# SCH_10_1HD_2021-11-26.net
KiCad netlist of a schematic drawn in EasyEDA
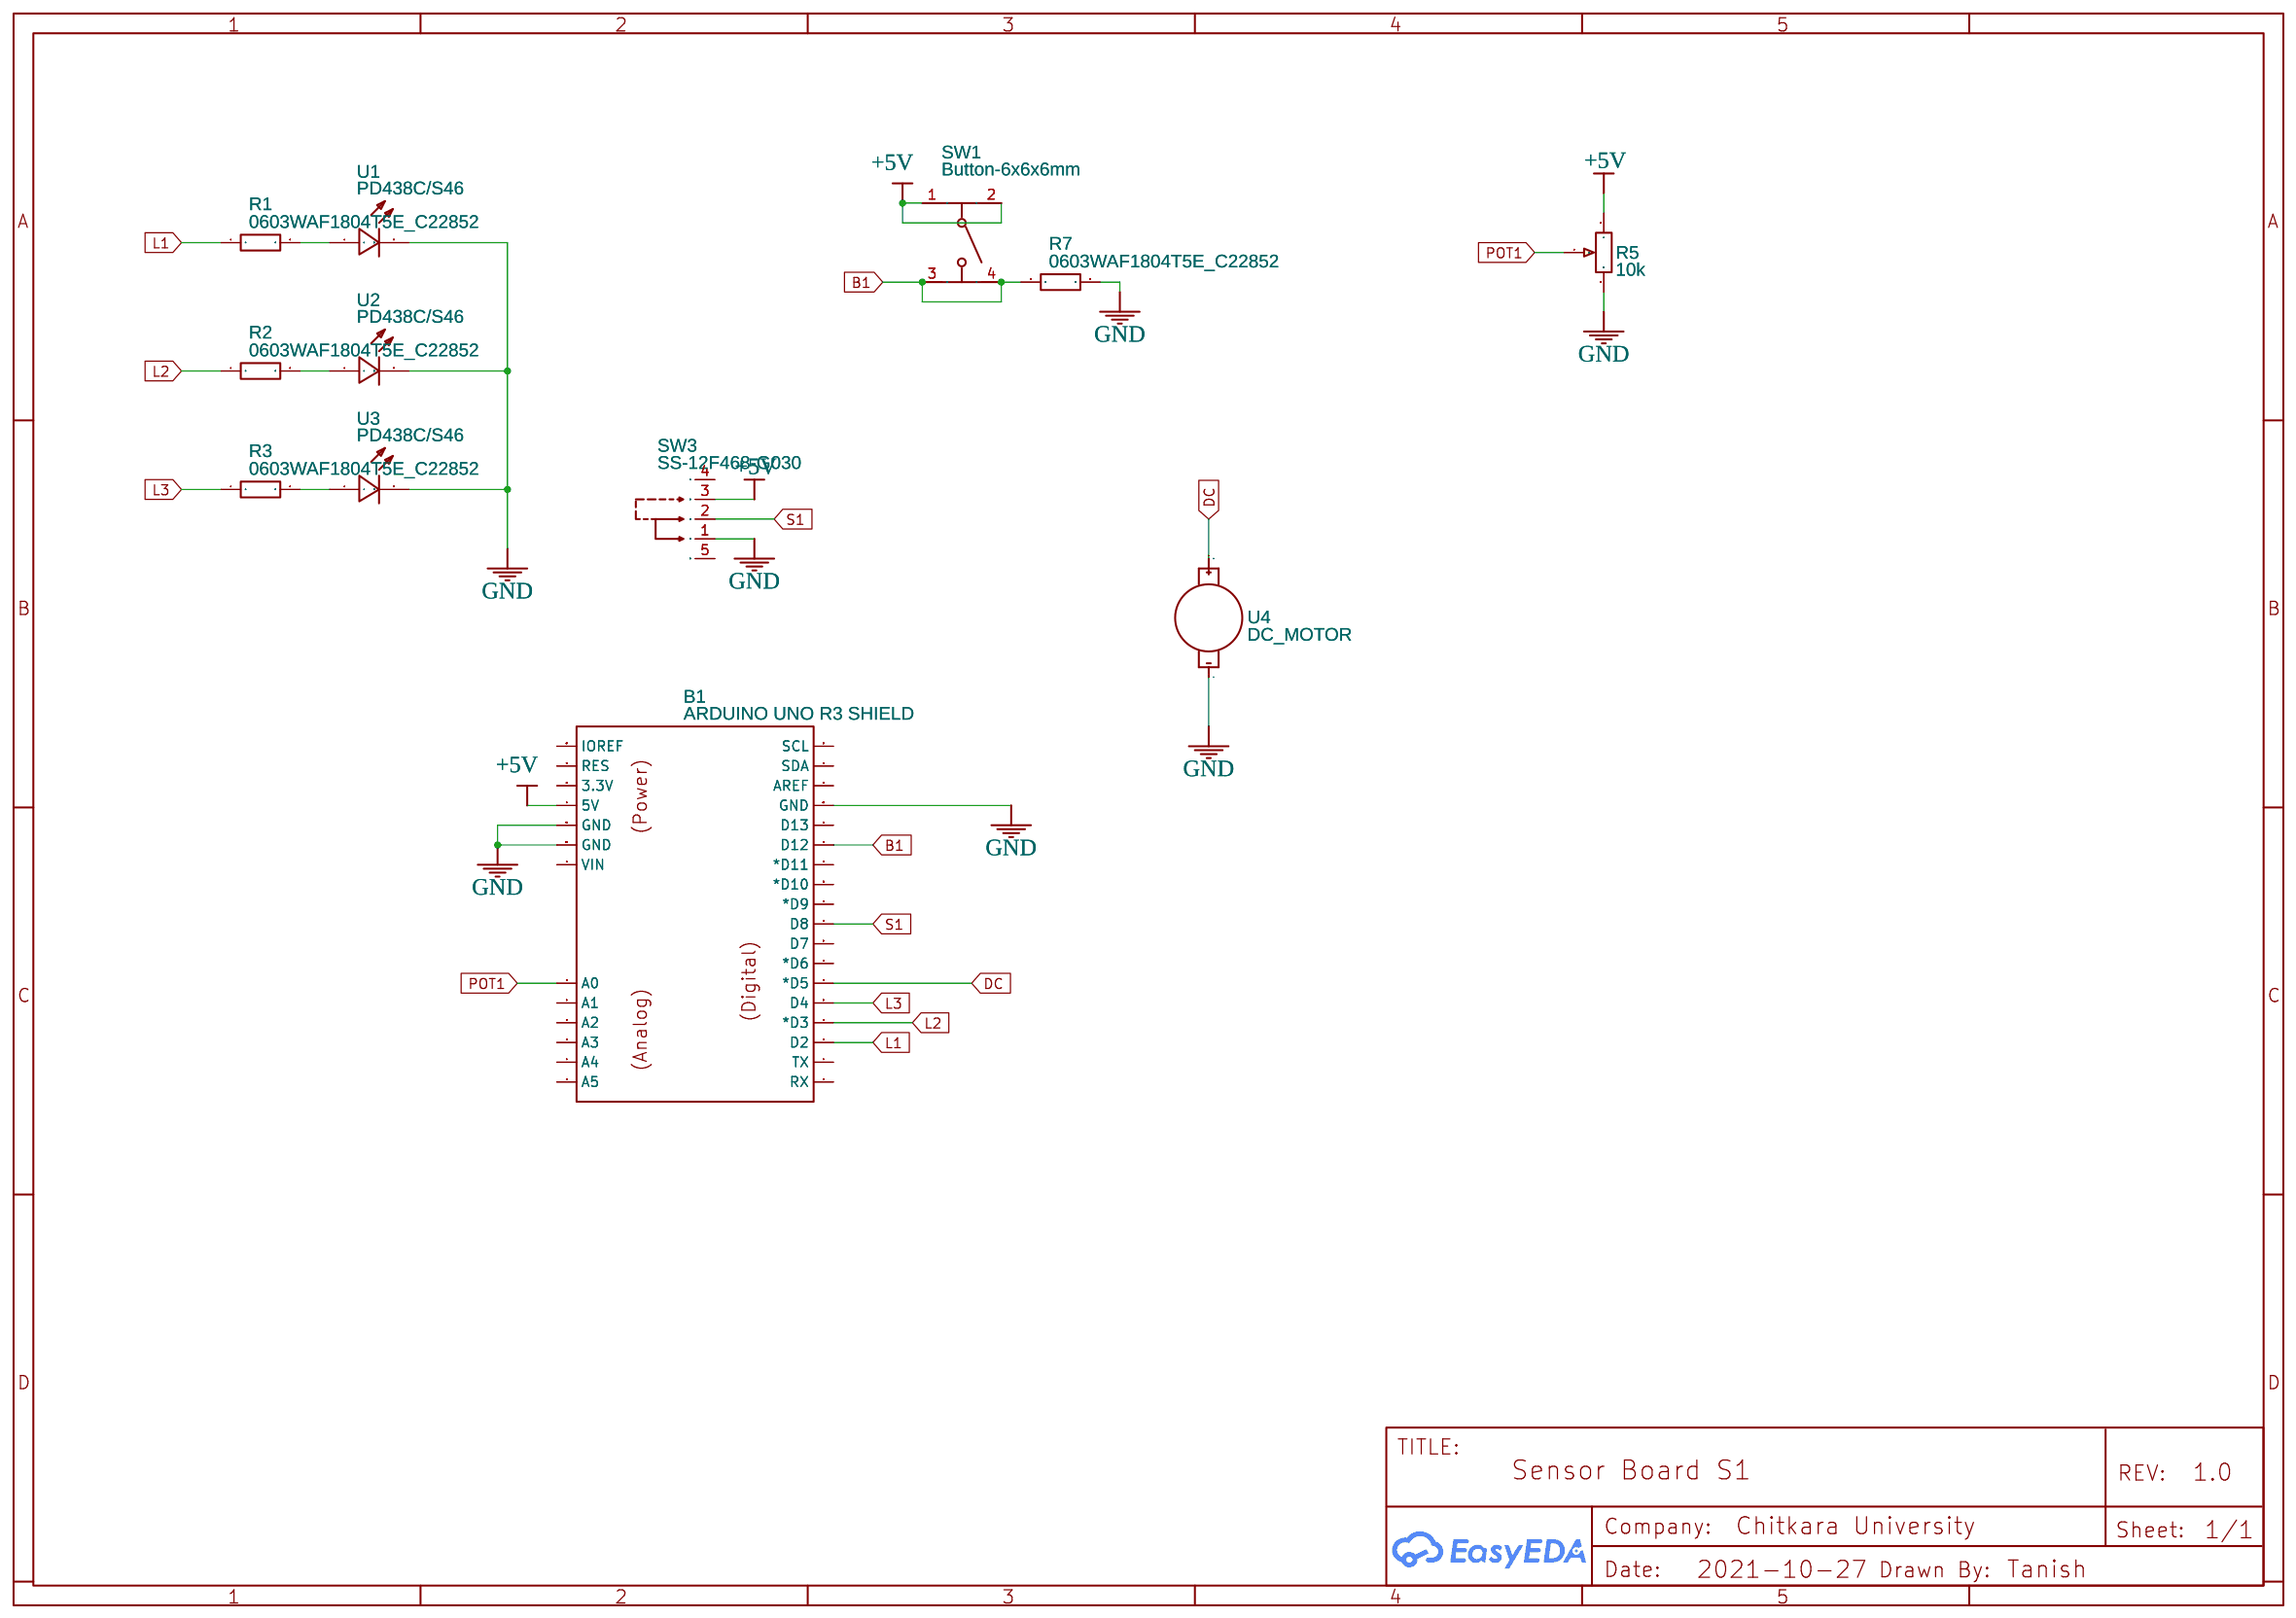
[diagram p0: schematic sheet]

(export (version "E")
  (design (tool "Eeschema 10.0.6"))
  (components
    (comp (ref "B1")
      (value "ARDUINO UNO R3 SHIELD")
      (fields (field (name "Manufacturer") "?"))
      (libsource (lib "") (part "ARDUINO UNO R3 SHIELD"))
    )
    (comp (ref "R1")
      (value "0603WAF1804T5E_C22852")
      (fields
        (field (name "BOM_Manufacturer Part") "0603WAF1804T5E")
        (field (name "BOM_Supplier Part") "C22852")
      )
      (libsource (lib "") (part "0603WAF1804T5E_C22852"))
    )
    (comp (ref "R2")
      (value "0603WAF1804T5E_C22852")
      (fields
        (field (name "BOM_Manufacturer Part") "0603WAF1804T5E")
        (field (name "BOM_Supplier Part") "C22852")
      )
      (libsource (lib "") (part "0603WAF1804T5E_C22852"))
    )
    (comp (ref "R3")
      (value "0603WAF1804T5E_C22852")
      (fields
        (field (name "BOM_Manufacturer Part") "0603WAF1804T5E")
        (field (name "BOM_Supplier Part") "C22852")
      )
      (libsource (lib "") (part "0603WAF1804T5E_C22852"))
    )
    (comp (ref "R5")
      (value "10k")
      (fields
        (field (name "BOM_Manufacturer Part") "3362F-1-103LF")
        (field (name "BOM_Supplier Part") "3362F-1-103LF-ND")
      )
      (libsource (lib "") (part "3362F-1-103LF"))
    )
    (comp (ref "R7")
      (value "0603WAF1804T5E_C22852")
      (fields
        (field (name "BOM_Manufacturer Part") "0603WAF1804T5E")
        (field (name "BOM_Supplier Part") "C22852")
      )
      (libsource (lib "") (part "0603WAF1804T5E_C22852"))
    )
    (comp (ref "SW1")
      (value "Button-6x6x6mm")
      (fields
        (field (name "BOM_Manufacturer Part") "Switch,6*6*6Plastic head,260G, 0.25mm,Straight line")
        (field (name "BOM_Supplier Part") "C71836")
      )
      (libsource (lib "") (part "Button-6x6x6mm"))
    )
    (comp (ref "SW3")
      (value "SS-12F468-G030")
      (fields (field (name "BOM_Supplier Part") "C2848904"))
      (libsource (lib "") (part "SS-12F468-G030"))
    )
    (comp (ref "U1")
      (value "PD438C/S46")
      (fields (field (name "BOM_Supplier Part") "C146238"))
      (libsource (lib "") (part "PD438C/S46"))
    )
    (comp (ref "U2")
      (value "PD438C/S46")
      (fields (field (name "BOM_Supplier Part") "C146238"))
      (libsource (lib "") (part "PD438C/S46"))
    )
    (comp (ref "U3")
      (value "PD438C/S46")
      (fields (field (name "BOM_Supplier Part") "C146238"))
      (libsource (lib "") (part "PD438C/S46"))
    )
    (comp (ref "U4") (value "DC_MOTOR") (libsource (lib "") (part "DC_MOTOR")))
  )
  (nets
    (net (code "1") (name "+5V") (class "Default")
      (node (ref "B1") (pin "5V") (pinfunction "5V_5V") (pintype "unspecified"))
      (node (ref "R5") (pin "1") (pinfunction "1_1") (pintype "input"))
      (node (ref "SW1") (pin "1") (pinfunction "1_1") (pintype "unspecified"))
      (node (ref "SW1") (pin "2") (pinfunction "2_2") (pintype "unspecified"))
      (node (ref "SW3") (pin "3") (pinfunction "3_3") (pintype "unspecified"))
    )
    (net (code "2") (name "B1") (class "Default")
      (node (ref "B1") (pin "D12") (pinfunction "D12_D12") (pintype "unspecified"))
      (node (ref "R7") (pin "1") (pinfunction "1_1") (pintype "input"))
      (node (ref "SW1") (pin "3") (pinfunction "3_3") (pintype "unspecified"))
      (node (ref "SW1") (pin "4") (pinfunction "4_4") (pintype "unspecified"))
    )
    (net (code "3") (name "DC") (class "Default")
      (node (ref "B1") (pin "D5") (pinfunction "*D5_D5") (pintype "unspecified"))
      (node (ref "U4") (pin "+") (pinfunction "+_+") (pintype "unspecified"))
    )
    (net (code "4") (name "GND") (class "Default")
      (node (ref "B1") (pin "GND@0") (pinfunction "GND_GND@0") (pintype "unspecified"))
      (node (ref "B1") (pin "GND@1") (pinfunction "GND_GND@1") (pintype "unspecified"))
      (node (ref "B1") (pin "GND@2") (pinfunction "GND_GND@2") (pintype "unspecified"))
      (node (ref "R5") (pin "3") (pinfunction "3_3") (pintype "input"))
      (node (ref "R7") (pin "2") (pinfunction "2_2") (pintype "input"))
      (node (ref "SW3") (pin "1") (pinfunction "1_1") (pintype "unspecified"))
      (node (ref "U1") (pin "2") (pinfunction "C_2") (pintype "unspecified"))
      (node (ref "U2") (pin "2") (pinfunction "C_2") (pintype "unspecified"))
      (node (ref "U3") (pin "2") (pinfunction "C_2") (pintype "unspecified"))
      (node (ref "U4") (pin "-") (pinfunction "-_-") (pintype "unspecified"))
    )
    (net (code "5") (name "L1") (class "Default")
      (node (ref "B1") (pin "D2") (pinfunction "D2_D2") (pintype "unspecified"))
      (node (ref "R1") (pin "1") (pinfunction "1_1") (pintype "input"))
    )
    (net (code "6") (name "L2") (class "Default")
      (node (ref "B1") (pin "D3") (pinfunction "*D3_D3") (pintype "unspecified"))
      (node (ref "R2") (pin "1") (pinfunction "1_1") (pintype "input"))
    )
    (net (code "7") (name "L3") (class "Default")
      (node (ref "B1") (pin "D4") (pinfunction "D4_D4") (pintype "unspecified"))
      (node (ref "R3") (pin "1") (pinfunction "1_1") (pintype "input"))
    )
    (net (code "8") (name "Net-(U1-A)") (class "Default")
      (node (ref "R1") (pin "2") (pinfunction "2_2") (pintype "input"))
      (node (ref "U1") (pin "1") (pinfunction "A_1") (pintype "unspecified"))
    )
    (net (code "9") (name "Net-(U2-A)") (class "Default")
      (node (ref "R2") (pin "2") (pinfunction "2_2") (pintype "input"))
      (node (ref "U2") (pin "1") (pinfunction "A_1") (pintype "unspecified"))
    )
    (net (code "10") (name "Net-(U3-A)") (class "Default")
      (node (ref "R3") (pin "2") (pinfunction "2_2") (pintype "input"))
      (node (ref "U3") (pin "1") (pinfunction "A_1") (pintype "unspecified"))
    )
    (net (code "11") (name "POT1") (class "Default")
      (node (ref "B1") (pin "A0") (pinfunction "A0_A0") (pintype "unspecified"))
      (node (ref "R5") (pin "2") (pinfunction "2_2") (pintype "input"))
    )
    (net (code "12") (name "S1") (class "Default")
      (node (ref "B1") (pin "D8") (pinfunction "D8_D8") (pintype "unspecified"))
      (node (ref "SW3") (pin "2") (pinfunction "2_2") (pintype "unspecified"))
    )
    (net (code "13") (name "unconnected-(B1-*D6-PadD6)") (class "Default")
      (node (ref "B1") (pin "D6") (pinfunction "*D6_D6") (pintype "unspecified"))
    )
    (net (code "14") (name "unconnected-(B1-*D9-PadD9)") (class "Default")
      (node (ref "B1") (pin "D9") (pinfunction "*D9_D9") (pintype "unspecified"))
    )
    (net (code "15") (name "unconnected-(B1-*D10-PadD10)") (class "Default")
      (node (ref "B1") (pin "D10") (pinfunction "*D10_D10") (pintype "unspecified"))
    )
    (net (code "16") (name "unconnected-(B1-*D11-PadD11)") (class "Default")
      (node (ref "B1") (pin "D11") (pinfunction "*D11_D11") (pintype "unspecified"))
    )
    (net (code "17") (name "unconnected-(B1-Pad3.3V)") (class "Default")
      (node (ref "B1") (pin "3.3V") (pinfunction "3.3V_3.3V") (pintype "unspecified"))
    )
    (net (code "18") (name "unconnected-(B1-PadA1)") (class "Default")
      (node (ref "B1") (pin "A1") (pinfunction "A1_A1") (pintype "unspecified"))
    )
    (net (code "19") (name "unconnected-(B1-PadA2)") (class "Default")
      (node (ref "B1") (pin "A2") (pinfunction "A2_A2") (pintype "unspecified"))
    )
    (net (code "20") (name "unconnected-(B1-PadA3)") (class "Default")
      (node (ref "B1") (pin "A3") (pinfunction "A3_A3") (pintype "unspecified"))
    )
    (net (code "21") (name "unconnected-(B1-PadA4)") (class "Default")
      (node (ref "B1") (pin "A4") (pinfunction "A4_A4") (pintype "unspecified"))
    )
    (net (code "22") (name "unconnected-(B1-PadA5)") (class "Default")
      (node (ref "B1") (pin "A5") (pinfunction "A5_A5") (pintype "unspecified"))
    )
    (net (code "23") (name "unconnected-(B1-PadAREF)") (class "Default")
      (node (ref "B1") (pin "AREF") (pinfunction "AREF_AREF") (pintype "unspecified"))
    )
    (net (code "24") (name "unconnected-(B1-PadD7)") (class "Default")
      (node (ref "B1") (pin "D7") (pinfunction "D7_D7") (pintype "unspecified"))
    )
    (net (code "25") (name "unconnected-(B1-PadD13)") (class "Default")
      (node (ref "B1") (pin "D13") (pinfunction "D13_D13") (pintype "unspecified"))
    )
    (net (code "26") (name "unconnected-(B1-PadIOREF)") (class "Default")
      (node (ref "B1") (pin "IOREF") (pinfunction "IOREF_IOREF") (pintype "unspecified"))
    )
    (net (code "27") (name "unconnected-(B1-PadRES)") (class "Default")
      (node (ref "B1") (pin "RES") (pinfunction "RES_RES") (pintype "unspecified"))
    )
    (net (code "28") (name "unconnected-(B1-PadRX)") (class "Default")
      (node (ref "B1") (pin "RX") (pinfunction "RX_RX") (pintype "unspecified"))
    )
    (net (code "29") (name "unconnected-(B1-PadSCL)") (class "Default")
      (node (ref "B1") (pin "SCL") (pinfunction "SCL_SCL") (pintype "unspecified"))
    )
    (net (code "30") (name "unconnected-(B1-PadSDA)") (class "Default")
      (node (ref "B1") (pin "SDA") (pinfunction "SDA_SDA") (pintype "unspecified"))
    )
    (net (code "31") (name "unconnected-(B1-PadTX)") (class "Default")
      (node (ref "B1") (pin "TX") (pinfunction "TX_TX") (pintype "unspecified"))
    )
    (net (code "32") (name "unconnected-(B1-PadVIN)") (class "Default")
      (node (ref "B1") (pin "VIN") (pinfunction "VIN_VIN") (pintype "unspecified"))
    )
    (net (code "33") (name "unconnected-(SW3-Pad4)") (class "Default")
      (node (ref "SW3") (pin "4") (pinfunction "4_4") (pintype "unspecified"))
    )
    (net (code "34") (name "unconnected-(SW3-Pad5)") (class "Default")
      (node (ref "SW3") (pin "5") (pinfunction "5_5") (pintype "unspecified"))
    )
  )
)
